# PCB.net
KiCad netlist of a schematic drawn in EAGLE
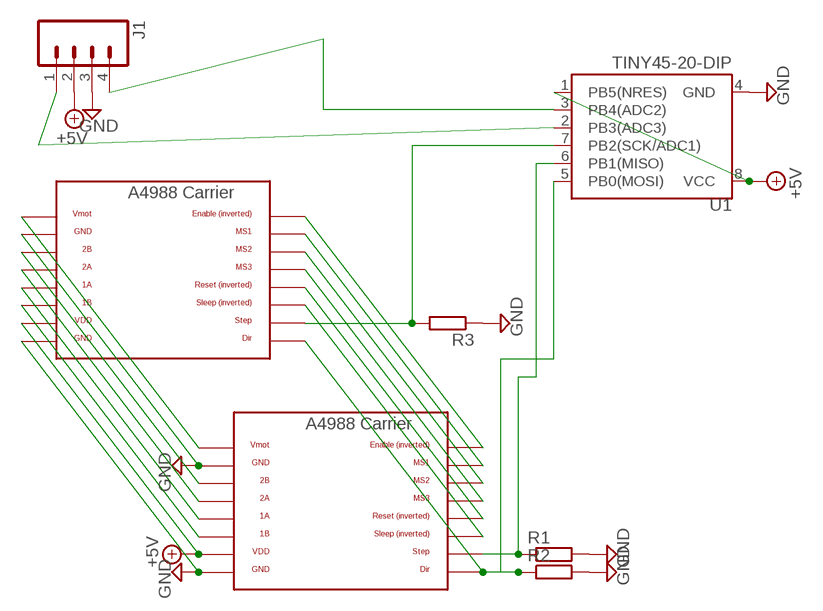
[diagram p0: schematic, sheet 1]

(export (version "E")
  (design (tool "Eeschema 10.0.6"))
  (components
    (comp (ref "J1")
      (value "M04JST-PTH-VERT")
      (footprint "eagle-import:JST-4-PTH-VERT")
      (libsource (lib "eagle-import") (part "M04JST-PTH-VERT"))
    )
    (comp (ref "R1")
      (value "R-EU_R0805")
      (footprint "eagle-import:R0805")
      (libsource (lib "eagle-import") (part "R-EU_R0805"))
    )
    (comp (ref "R2")
      (value "R-EU_R0805")
      (footprint "eagle-import:R0805")
      (libsource (lib "eagle-import") (part "R-EU_R0805"))
    )
    (comp (ref "R3")
      (value "R-EU_R0805")
      (footprint "eagle-import:R0805")
      (libsource (lib "eagle-import") (part "R-EU_R0805"))
    )
    (comp (ref "U$1")
      (value "A4988BREAKOUT")
      (footprint "eagle-import:A4988BREAKOUT")
      (libsource (lib "eagle-import") (part "A4988BREAKOUT"))
    )
    (comp (ref "U$2")
      (value "A4988BREAKOUT")
      (footprint "eagle-import:A4988BREAKOUT")
      (libsource (lib "eagle-import") (part "A4988BREAKOUT"))
    )
    (comp (ref "U1")
      (value "TINY45-20-DIP")
      (footprint "eagle-import:DIP08")
      (libsource (lib "eagle-import") (part "ATTINY45TINY45-20-DIP"))
    )
  )
  (nets
    (net (code "1") (name "+5V") (class "Default")
      (node (ref "J1") (pin "2") (pinfunction "2_2") (pintype "passive"))
      (node (ref "U$1") (pin "VDD") (pinfunction "VDD_VDD") (pintype "power_in"))
      (node (ref "U$2") (pin "VDD") (pinfunction "VDD_VDD") (pintype "power_in"))
      (node (ref "U1") (pin "1") (pinfunction "PB5(NRES)_1") (pintype "bidirectional"))
      (node (ref "U1") (pin "8") (pinfunction "VCC_8") (pintype "bidirectional"))
    )
    (net (code "2") (name "GND") (class "Default")
      (node (ref "J1") (pin "3") (pinfunction "3_3") (pintype "passive"))
      (node (ref "R1") (pin "2") (pinfunction "2_2") (pintype "passive"))
      (node (ref "R2") (pin "2") (pinfunction "2_2") (pintype "passive"))
      (node (ref "R3") (pin "1") (pinfunction "1_1") (pintype "passive"))
      (node (ref "U$1") (pin "GND") (pinfunction "GND_GND") (pintype "power_in"))
      (node (ref "U$1") (pin "GND@0") (pinfunction "GND_GND@0") (pintype "power_in"))
      (node (ref "U$2") (pin "GND") (pinfunction "GND_GND") (pintype "power_in"))
      (node (ref "U$2") (pin "GND@0") (pinfunction "GND_GND@0") (pintype "power_in"))
      (node (ref "U1") (pin "4") (pinfunction "GND_4") (pintype "bidirectional"))
    )
    (net (code "3") (name "Net-(U$1-Pad1A)") (class "Default")
      (node (ref "U$1") (pin "1A") (pinfunction "1A_1A") (pintype "output"))
      (node (ref "U$2") (pin "1A") (pinfunction "1A_1A") (pintype "output"))
    )
    (net (code "4") (name "Net-(U$1-Pad1B)") (class "Default")
      (node (ref "U$1") (pin "1B") (pinfunction "1B_1B") (pintype "output"))
      (node (ref "U$2") (pin "1B") (pinfunction "1B_1B") (pintype "output"))
    )
    (net (code "5") (name "Net-(U$1-Pad2A)") (class "Default")
      (node (ref "U$1") (pin "2A") (pinfunction "2A_2A") (pintype "output"))
      (node (ref "U$2") (pin "2A") (pinfunction "2A_2A") (pintype "output"))
    )
    (net (code "6") (name "Net-(U$1-Pad2B)") (class "Default")
      (node (ref "U$1") (pin "2B") (pinfunction "2B_2B") (pintype "output"))
      (node (ref "U$2") (pin "2B") (pinfunction "2B_2B") (pintype "output"))
    )
    (net (code "7") (name "Net-(U$1-PadEN)") (class "Default")
      (node (ref "U$1") (pin "EN") (pinfunction "EN_EN") (pintype "input"))
      (node (ref "U$2") (pin "EN") (pinfunction "EN_EN") (pintype "input"))
    )
    (net (code "8") (name "Net-(U$1-PadMS1)") (class "Default")
      (node (ref "U$1") (pin "MS1") (pinfunction "MS1_MS1") (pintype "input"))
      (node (ref "U$2") (pin "MS1") (pinfunction "MS1_MS1") (pintype "input"))
    )
    (net (code "9") (name "Net-(U$1-PadMS2)") (class "Default")
      (node (ref "U$1") (pin "MS2") (pinfunction "MS2_MS2") (pintype "input"))
      (node (ref "U$2") (pin "MS2") (pinfunction "MS2_MS2") (pintype "input"))
    )
    (net (code "10") (name "Net-(U$1-PadMS3)") (class "Default")
      (node (ref "U$1") (pin "MS3") (pinfunction "MS3_MS3") (pintype "input"))
      (node (ref "U$2") (pin "MS3") (pinfunction "MS3_MS3") (pintype "input"))
    )
    (net (code "11") (name "Net-(U$1-PadRST)") (class "Default")
      (node (ref "U$1") (pin "RST") (pinfunction "RST_RST") (pintype "input"))
      (node (ref "U$2") (pin "RST") (pinfunction "RST_RST") (pintype "input"))
    )
    (net (code "12") (name "Net-(U$1-PadVMOT)") (class "Default")
      (node (ref "U$1") (pin "VMOT") (pinfunction "VMOT_VMOT") (pintype "power_in"))
      (node (ref "U$2") (pin "VMOT") (pinfunction "VMOT_VMOT") (pintype "power_in"))
    )
    (net (code "13") (name "Net-(U$1-SLEEP)") (class "Default")
      (node (ref "U$1") (pin "SLP") (pinfunction "SLEEP_SLP") (pintype "input"))
      (node (ref "U$2") (pin "SLP") (pinfunction "SLEEP_SLP") (pintype "input"))
    )
    (net (code "14") (name "Net-(U1-PB0(MOSI))") (class "Default")
      (node (ref "R2") (pin "1") (pinfunction "1_1") (pintype "passive"))
      (node (ref "U$1") (pin "DIR") (pinfunction "DIR_DIR") (pintype "input"))
      (node (ref "U$2") (pin "DIR") (pinfunction "DIR_DIR") (pintype "input"))
      (node (ref "U1") (pin "5") (pinfunction "PB0(MOSI)_5") (pintype "bidirectional"))
    )
    (net (code "15") (name "Net-(U1-PB1(MISO))") (class "Default")
      (node (ref "R1") (pin "1") (pinfunction "1_1") (pintype "passive"))
      (node (ref "U$2") (pin "STEP") (pinfunction "STEP_STEP") (pintype "input"))
      (node (ref "U1") (pin "6") (pinfunction "PB1(MISO)_6") (pintype "bidirectional"))
    )
    (net (code "16") (name "Net-(U1-PB2(SCK{slash}ADC1))") (class "Default")
      (node (ref "R3") (pin "2") (pinfunction "2_2") (pintype "passive"))
      (node (ref "U$1") (pin "STEP") (pinfunction "STEP_STEP") (pintype "input"))
      (node (ref "U1") (pin "7") (pinfunction "PB2(SCK/ADC1)_7") (pintype "bidirectional"))
    )
    (net (code "17") (name "Net-(U1-PB3(ADC3))") (class "Default")
      (node (ref "J1") (pin "1") (pinfunction "1_1") (pintype "passive"))
      (node (ref "U1") (pin "2") (pinfunction "PB3(ADC3)_2") (pintype "bidirectional"))
    )
    (net (code "18") (name "Net-(U1-PB4(ADC2))") (class "Default")
      (node (ref "J1") (pin "4") (pinfunction "4_4") (pintype "passive"))
      (node (ref "U1") (pin "3") (pinfunction "PB4(ADC2)_3") (pintype "bidirectional"))
    )
  )
)
